# Schematic.net
KiCad netlist of a schematic drawn in Altium Designer
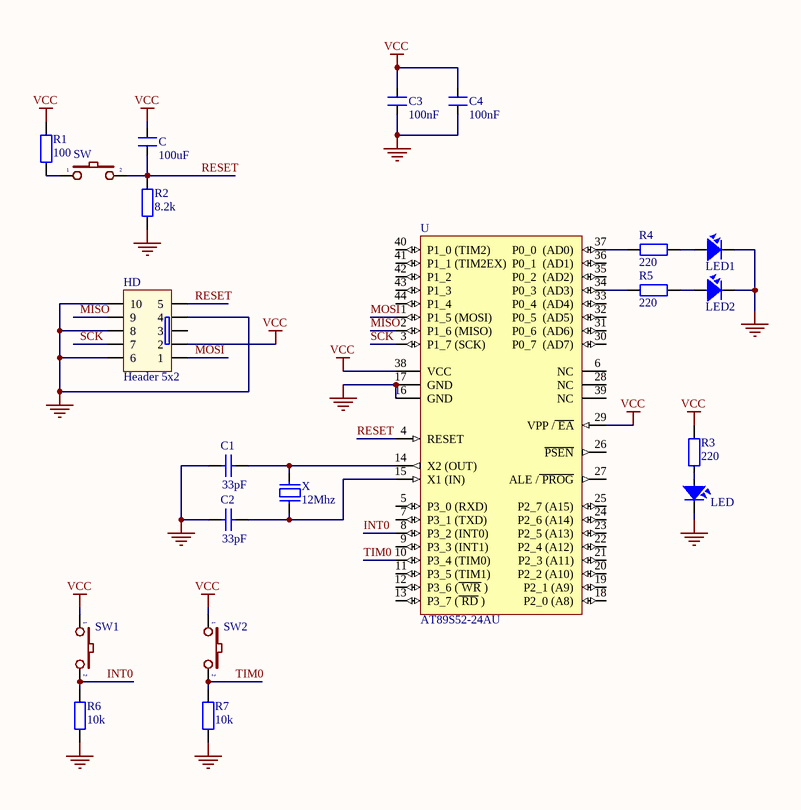
[diagram p0: Schematic.SchDoc]

(export (version "E")
  (design (tool "Eeschema 10.0.6"))
  (components
    (comp (ref "C")
      (value "100uF")
      (footprint "SM-Cap-1206")
      (fields (field (name "DESIGNED BY") "VanDungEvn"))
      (libsource (lib "echipkool-com-library") (part "CN"))
    )
    (comp (ref "C1")
      (value "33pF")
      (footprint "C0805")
      (description "Capacitor")
      (fields (field (name "PUBLISHER") "Altium Limited"))
      (libsource (lib "My Library") (part "CapSMD"))
    )
    (comp (ref "C2")
      (value "33pF")
      (footprint "C0805")
      (description "Capacitor")
      (fields (field (name "PUBLISHER") "Altium Limited"))
      (libsource (lib "My Library") (part "CapSMD"))
    )
    (comp (ref "C3")
      (value "100nF")
      (footprint "SM-Cap-1206")
      (fields (field (name "DESIGNED BY") "VanDungEvn"))
      (libsource (lib "echipkool-com-library") (part "CN"))
    )
    (comp (ref "C4")
      (value "100nF")
      (footprint "SM-Cap-1206")
      (fields (field (name "DESIGNED BY") "VanDungEvn"))
      (libsource (lib "echipkool-com-library") (part "CN"))
    )
    (comp (ref "HD")
      (value "Header 5x2")
      (footprint "Hed2X5")
      (libsource (lib "echipkool-com-library") (part "HED5x2"))
    )
    (comp (ref "LED")
      (value "LED")
      (footprint "LED-0805-Red")
      (libsource (lib "LIBRARYALT") (part "LED SMD"))
    )
    (comp (ref "LED1")
      (value "LED1")
      (footprint "LED-0805-Red")
      (libsource (lib "LIBRARYALT") (part "LED SMD"))
    )
    (comp (ref "LED2")
      (value "LED")
      (footprint "LED-0805-Red")
      (libsource (lib "LIBRARYALT") (part "LED SMD"))
    )
    (comp (ref "R1")
      (value "100")
      (footprint "SM-RES-0805")
      (description "Resistor 1/4W")
      (libsource (lib "echipkool-com-library") (part "R1/4W"))
    )
    (comp (ref "R2")
      (value "8.2k")
      (footprint "SM-RES-0805")
      (description "Resistor 1/4W")
      (libsource (lib "echipkool-com-library") (part "R1/4W"))
    )
    (comp (ref "R3")
      (value "220")
      (footprint "SM-RES-0805")
      (description "Resistor 1/4W")
      (libsource (lib "echipkool-com-library") (part "R1/4W"))
    )
    (comp (ref "R4")
      (value "220")
      (footprint "SM-RES-0805")
      (description "Resistor 1/4W")
      (libsource (lib "echipkool-com-library") (part "R1/4W"))
    )
    (comp (ref "R5")
      (value "220")
      (footprint "SM-RES-0805")
      (description "Resistor 1/4W")
      (libsource (lib "echipkool-com-library") (part "R1/4W"))
    )
    (comp (ref "R6")
      (value "10k")
      (footprint "SM-RES-0805")
      (description "Resistor 1/4W")
      (libsource (lib "echipkool-com-library") (part "R1/4W"))
    )
    (comp (ref "R7")
      (value "10k")
      (footprint "SM-RES-0805")
      (description "Resistor 1/4W")
      (libsource (lib "echipkool-com-library") (part "R1/4W"))
    )
    (comp (ref "SW")
      (value "~")
      (footprint "SW1-SMD")
      (description "Switch button 2 pin")
      (libsource (lib "LIBRARYALT") (part "SW2"))
    )
    (comp (ref "SW1")
      (value "~")
      (footprint "SW1-SMD")
      (description "Switch button 2 pin")
      (libsource (lib "LIBRARYALT") (part "SW2"))
    )
    (comp (ref "SW2")
      (value "~")
      (footprint "SW1-SMD")
      (description "Switch button 2 pin")
      (libsource (lib "LIBRARYALT") (part "SW2"))
    )
    (comp (ref "U")
      (value "AT89S52-24AU")
      (footprint "TQFP44")
      (description "Atmel 8 Bit Micro 4.0-5.5V 24MHz -40 to +80 Deg C 44TQFP (44A) Package GREEN OPTION")
      (libsource (lib "LIBRARYALT") (part "AT89S52-24AU"))
    )
    (comp (ref "X")
      (value "12Mhz")
      (footprint "XTAL-RU49/4")
      (description "Crystal, 32.768 KHz, -40 to 85 degC, 3.2 x 1.5 x 0.9 mm SMD")
      (libsource (lib "LIBRARYALT") (part "XT2"))
    )
  )
  (nets
    (net (code "1") (name "/INT0") (class "Default")
      (node (ref "R6") (pin "2") (pinfunction "2_2") (pintype "passive"))
      (node (ref "SW1") (pin "2") (pinfunction "2_2") (pintype "passive"))
      (node (ref "U") (pin "8") (pinfunction "P3_2_(INT0)_8") (pintype "bidirectional"))
    )
    (net (code "2") (name "/MISO") (class "Default")
      (node (ref "HD") (pin "9") (pinfunction "9_9") (pintype "passive"))
      (node (ref "U") (pin "2") (pinfunction "P1_6_(MISO)_2") (pintype "bidirectional"))
    )
    (net (code "3") (name "/MOSI") (class "Default")
      (node (ref "HD") (pin "1") (pinfunction "1_1") (pintype "passive"))
      (node (ref "U") (pin "1") (pinfunction "P1_5_(MOSI)_1") (pintype "bidirectional"))
    )
    (net (code "4") (name "/RESET") (class "Default")
      (node (ref "C") (pin "2") (pinfunction "2_2") (pintype "passive"))
      (node (ref "HD") (pin "5") (pinfunction "5_5") (pintype "passive"))
      (node (ref "R2") (pin "2") (pinfunction "2_2") (pintype "passive"))
      (node (ref "SW") (pin "2") (pinfunction "2_2") (pintype "passive"))
      (node (ref "U") (pin "4") (pinfunction "RESET_4") (pintype "input"))
    )
    (net (code "5") (name "/SCK") (class "Default")
      (node (ref "HD") (pin "7") (pinfunction "7_7") (pintype "passive"))
      (node (ref "U") (pin "3") (pinfunction "P1_7_(SCK)_3") (pintype "bidirectional"))
    )
    (net (code "6") (name "/TIM0") (class "Default")
      (node (ref "R7") (pin "2") (pinfunction "2_2") (pintype "passive"))
      (node (ref "SW2") (pin "2") (pinfunction "2_2") (pintype "passive"))
      (node (ref "U") (pin "10") (pinfunction "P3_4_(TIM0)_10") (pintype "bidirectional"))
    )
    (net (code "7") (name "GND") (class "Default")
      (node (ref "C1") (pin "1") (pinfunction "1_1") (pintype "passive"))
      (node (ref "C2") (pin "1") (pinfunction "1_1") (pintype "passive"))
      (node (ref "C3") (pin "1") (pinfunction "1_1") (pintype "passive"))
      (node (ref "C4") (pin "1") (pinfunction "1_1") (pintype "passive"))
      (node (ref "HD") (pin "10") (pinfunction "10_10") (pintype "passive"))
      (node (ref "HD") (pin "4") (pinfunction "4_4") (pintype "passive"))
      (node (ref "HD") (pin "6") (pinfunction "6_6") (pintype "passive"))
      (node (ref "HD") (pin "8") (pinfunction "8_8") (pintype "passive"))
      (node (ref "LED") (pin "2") (pinfunction "2_2") (pintype "passive"))
      (node (ref "LED1") (pin "2") (pinfunction "2_2") (pintype "passive"))
      (node (ref "LED2") (pin "2") (pinfunction "2_2") (pintype "passive"))
      (node (ref "R2") (pin "1") (pinfunction "1_1") (pintype "passive"))
      (node (ref "R6") (pin "1") (pinfunction "1_1") (pintype "passive"))
      (node (ref "R7") (pin "1") (pinfunction "1_1") (pintype "passive"))
      (node (ref "U") (pin "16") (pinfunction "GND_16") (pintype "power_in"))
      (node (ref "U") (pin "17") (pinfunction "GND_17") (pintype "power_in"))
    )
    (net (code "8") (name "Net-(LED-Pad1)") (class "Default")
      (node (ref "LED") (pin "1") (pinfunction "1_1") (pintype "passive"))
      (node (ref "R3") (pin "1") (pinfunction "1_1") (pintype "passive"))
    )
    (net (code "9") (name "Net-(LED1-Pad1)") (class "Default")
      (node (ref "LED1") (pin "1") (pinfunction "1_1") (pintype "passive"))
      (node (ref "R4") (pin "2") (pinfunction "2_2") (pintype "passive"))
    )
    (net (code "10") (name "Net-(LED2-Pad1)") (class "Default")
      (node (ref "LED2") (pin "1") (pinfunction "1_1") (pintype "passive"))
      (node (ref "R5") (pin "2") (pinfunction "2_2") (pintype "passive"))
    )
    (net (code "11") (name "Net-(R1-Pad1)") (class "Default")
      (node (ref "R1") (pin "1") (pinfunction "1_1") (pintype "passive"))
      (node (ref "SW") (pin "1") (pinfunction "1_1") (pintype "passive"))
    )
    (net (code "12") (name "Net-(U-P0_0__(AD0))") (class "Default")
      (node (ref "R4") (pin "1") (pinfunction "1_1") (pintype "passive"))
      (node (ref "U") (pin "37") (pinfunction "P0_0__(AD0)_37") (pintype "bidirectional"))
    )
    (net (code "13") (name "Net-(U-P0_3__(AD3))") (class "Default")
      (node (ref "R5") (pin "1") (pinfunction "1_1") (pintype "passive"))
      (node (ref "U") (pin "34") (pinfunction "P0_3__(AD3)_34") (pintype "bidirectional"))
    )
    (net (code "14") (name "Net-(U-X1_(IN))") (class "Default")
      (node (ref "C2") (pin "2") (pinfunction "2_2") (pintype "passive"))
      (node (ref "U") (pin "15") (pinfunction "X1_(IN)_15") (pintype "input"))
      (node (ref "X") (pin "1") (pinfunction "1_1") (pintype "passive"))
    )
    (net (code "15") (name "Net-(U-X2_(OUT))") (class "Default")
      (node (ref "C1") (pin "2") (pinfunction "2_2") (pintype "passive"))
      (node (ref "U") (pin "14") (pinfunction "X2_(OUT)_14") (pintype "output"))
      (node (ref "X") (pin "2") (pinfunction "2_2") (pintype "passive"))
    )
    (net (code "16") (name "VCC") (class "Default")
      (node (ref "C") (pin "1") (pinfunction "1_1") (pintype "passive"))
      (node (ref "C3") (pin "2") (pinfunction "2_2") (pintype "passive"))
      (node (ref "C4") (pin "2") (pinfunction "2_2") (pintype "passive"))
      (node (ref "HD") (pin "2") (pinfunction "2_2") (pintype "passive"))
      (node (ref "R1") (pin "2") (pinfunction "2_2") (pintype "passive"))
      (node (ref "R3") (pin "2") (pinfunction "2_2") (pintype "passive"))
      (node (ref "SW1") (pin "1") (pinfunction "1_1") (pintype "passive"))
      (node (ref "SW2") (pin "1") (pinfunction "1_1") (pintype "passive"))
      (node (ref "U") (pin "29") (pinfunction "VPP_/~{_EA}_29") (pintype "input"))
      (node (ref "U") (pin "38") (pinfunction "VCC_38") (pintype "power_in"))
    )
    (net (code "17") (name "unconnected-(HD-Pad3)") (class "Default")
      (node (ref "HD") (pin "3") (pinfunction "3_3") (pintype "passive"))
    )
    (net (code "18") (name "unconnected-(U-ALE_{slash}~{_PROG}-Pad27)") (class "Default")
      (node (ref "U") (pin "27") (pinfunction "ALE_/~{_PROG}_27") (pintype "output"))
    )
    (net (code "19") (name "unconnected-(U-NC-Pad6)") (class "Default")
      (node (ref "U") (pin "6") (pinfunction "NC_6") (pintype "passive"))
    )
    (net (code "20") (name "unconnected-(U-NC-Pad28)") (class "Default")
      (node (ref "U") (pin "28") (pinfunction "NC_28") (pintype "passive"))
    )
    (net (code "21") (name "unconnected-(U-NC-Pad39)") (class "Default")
      (node (ref "U") (pin "39") (pinfunction "NC_39") (pintype "passive"))
    )
    (net (code "22") (name "unconnected-(U-P0_1__(AD1)-Pad36)") (class "Default")
      (node (ref "U") (pin "36") (pinfunction "P0_1__(AD1)_36") (pintype "bidirectional"))
    )
    (net (code "23") (name "unconnected-(U-P0_2__(AD2)-Pad35)") (class "Default")
      (node (ref "U") (pin "35") (pinfunction "P0_2__(AD2)_35") (pintype "bidirectional"))
    )
    (net (code "24") (name "unconnected-(U-P0_4__(AD4)-Pad33)") (class "Default")
      (node (ref "U") (pin "33") (pinfunction "P0_4__(AD4)_33") (pintype "bidirectional"))
    )
    (net (code "25") (name "unconnected-(U-P0_5__(AD5)-Pad32)") (class "Default")
      (node (ref "U") (pin "32") (pinfunction "P0_5__(AD5)_32") (pintype "bidirectional"))
    )
    (net (code "26") (name "unconnected-(U-P0_6__(AD6)-Pad31)") (class "Default")
      (node (ref "U") (pin "31") (pinfunction "P0_6__(AD6)_31") (pintype "bidirectional"))
    )
    (net (code "27") (name "unconnected-(U-P0_7__(AD7)-Pad30)") (class "Default")
      (node (ref "U") (pin "30") (pinfunction "P0_7__(AD7)_30") (pintype "bidirectional"))
    )
    (net (code "28") (name "unconnected-(U-P1_0_(TIM2)-Pad40)") (class "Default")
      (node (ref "U") (pin "40") (pinfunction "P1_0_(TIM2)_40") (pintype "bidirectional"))
    )
    (net (code "29") (name "unconnected-(U-P1_1_(TIM2EX)-Pad41)") (class "Default")
      (node (ref "U") (pin "41") (pinfunction "P1_1_(TIM2EX)_41") (pintype "bidirectional"))
    )
    (net (code "30") (name "unconnected-(U-P1_2-Pad42)") (class "Default")
      (node (ref "U") (pin "42") (pinfunction "P1_2_42") (pintype "bidirectional"))
    )
    (net (code "31") (name "unconnected-(U-P1_3-Pad43)") (class "Default")
      (node (ref "U") (pin "43") (pinfunction "P1_3_43") (pintype "bidirectional"))
    )
    (net (code "32") (name "unconnected-(U-P1_4-Pad44)") (class "Default")
      (node (ref "U") (pin "44") (pinfunction "P1_4_44") (pintype "bidirectional"))
    )
    (net (code "33") (name "unconnected-(U-P2_0_(A8)-Pad18)") (class "Default")
      (node (ref "U") (pin "18") (pinfunction "P2_0_(A8)_18") (pintype "bidirectional"))
    )
    (net (code "34") (name "unconnected-(U-P2_1_(A9)-Pad19)") (class "Default")
      (node (ref "U") (pin "19") (pinfunction "P2_1_(A9)_19") (pintype "bidirectional"))
    )
    (net (code "35") (name "unconnected-(U-P2_2_(A10)-Pad20)") (class "Default")
      (node (ref "U") (pin "20") (pinfunction "P2_2_(A10)_20") (pintype "bidirectional"))
    )
    (net (code "36") (name "unconnected-(U-P2_3_(A11)-Pad21)") (class "Default")
      (node (ref "U") (pin "21") (pinfunction "P2_3_(A11)_21") (pintype "bidirectional"))
    )
    (net (code "37") (name "unconnected-(U-P2_4_(A12)-Pad22)") (class "Default")
      (node (ref "U") (pin "22") (pinfunction "P2_4_(A12)_22") (pintype "bidirectional"))
    )
    (net (code "38") (name "unconnected-(U-P2_5_(A13)-Pad23)") (class "Default")
      (node (ref "U") (pin "23") (pinfunction "P2_5_(A13)_23") (pintype "bidirectional"))
    )
    (net (code "39") (name "unconnected-(U-P2_6_(A14)-Pad24)") (class "Default")
      (node (ref "U") (pin "24") (pinfunction "P2_6_(A14)_24") (pintype "bidirectional"))
    )
    (net (code "40") (name "unconnected-(U-P2_7_(A15)-Pad25)") (class "Default")
      (node (ref "U") (pin "25") (pinfunction "P2_7_(A15)_25") (pintype "bidirectional"))
    )
    (net (code "41") (name "unconnected-(U-P3_0_(RXD)-Pad5)") (class "Default")
      (node (ref "U") (pin "5") (pinfunction "P3_0_(RXD)_5") (pintype "bidirectional"))
    )
    (net (code "42") (name "unconnected-(U-P3_1_(TXD)-Pad7)") (class "Default")
      (node (ref "U") (pin "7") (pinfunction "P3_1_(TXD)_7") (pintype "bidirectional"))
    )
    (net (code "43") (name "unconnected-(U-P3_3_(INT1)-Pad9)") (class "Default")
      (node (ref "U") (pin "9") (pinfunction "P3_3_(INT1)_9") (pintype "bidirectional"))
    )
    (net (code "44") (name "unconnected-(U-P3_5_(TIM1)-Pad11)") (class "Default")
      (node (ref "U") (pin "11") (pinfunction "P3_5_(TIM1)_11") (pintype "bidirectional"))
    )
    (net (code "45") (name "unconnected-(U-P3_6_(~{_WR}_)-Pad12)") (class "Default")
      (node (ref "U") (pin "12") (pinfunction "P3_6_(~{_WR}_)_12") (pintype "bidirectional"))
    )
    (net (code "46") (name "unconnected-(U-P3_7_(~{_RD}_)-Pad13)") (class "Default")
      (node (ref "U") (pin "13") (pinfunction "P3_7_(~{_RD}_)_13") (pintype "bidirectional"))
    )
    (net (code "47") (name "unconnected-(U-PSEN-Pad26)") (class "Default")
      (node (ref "U") (pin "26") (pinfunction "PSEN_26") (pintype "output"))
    )
  )
)
